# HyperRAM2.net
KiCad netlist of a schematic drawn in Altium Designer
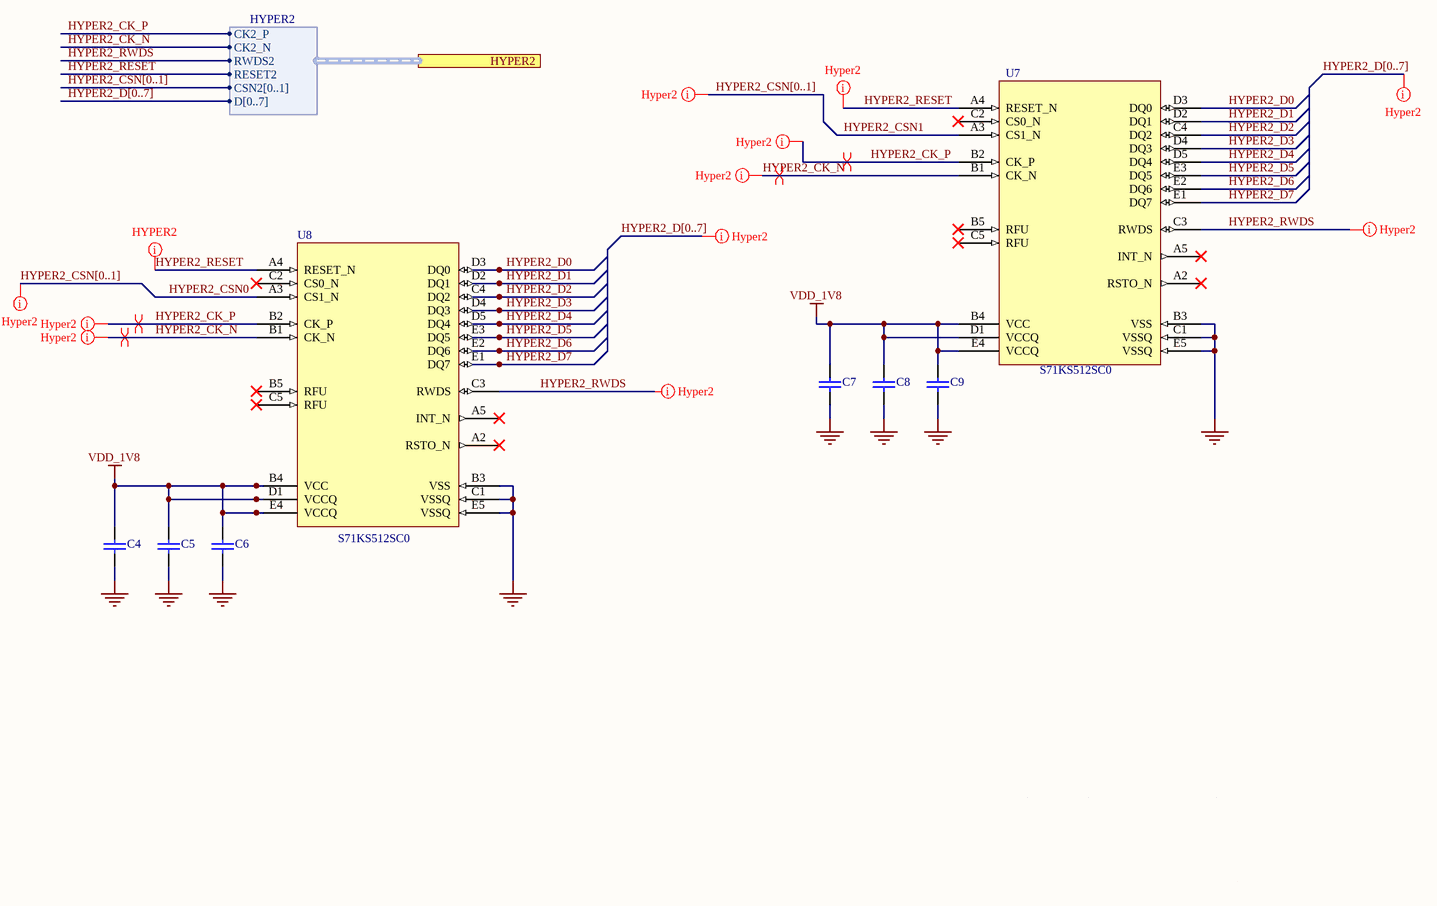
[diagram p0: HyperRAM2.SchDoc]

(export (version "E")
  (design (tool "Eeschema 10.0.6"))
  (components
    (comp (ref "C4")
      (value "VJ0603Y104KNXAO")
      (footprint "CAPC1608X92X38LL15T08")
      (fields (field (name "MANUFACTURER") "Vitramon"))
      (libsource (lib "Altium Content Vault") (part "CAP"))
    )
    (comp (ref "C5")
      (value "VJ0603Y104KNXAO")
      (footprint "CAPC1608X92X38LL15T08")
      (fields (field (name "MANUFACTURER") "Vitramon"))
      (libsource (lib "Altium Content Vault") (part "CAP"))
    )
    (comp (ref "C6")
      (value "VJ0603Y104KNXAO")
      (footprint "CAPC1608X92X38LL15T08")
      (fields (field (name "MANUFACTURER") "Vitramon"))
      (libsource (lib "Altium Content Vault") (part "CAP"))
    )
    (comp (ref "C7")
      (value "VJ0603Y104KNXAO")
      (footprint "CAPC1608X92X38LL15T08")
      (description "100nF")
      (fields (field (name "MANUFACTURER") "Vitramon"))
      (libsource (lib "Altium Content Vault") (part "CAP"))
    )
    (comp (ref "C8")
      (value "VJ0603Y104KNXAO")
      (footprint "CAPC1608X92X38LL15T08")
      (fields (field (name "MANUFACTURER") "Vitramon"))
      (libsource (lib "Altium Content Vault") (part "CAP"))
    )
    (comp (ref "C9")
      (value "VJ0603Y104KNXAO")
      (footprint "CAPC1608X92X38LL15T08")
      (fields (field (name "MANUFACTURER") "Vitramon"))
      (libsource (lib "Altium Content Vault") (part "CAP"))
    )
    (comp (ref "U7")
      (value "S71KS512SC0")
      (footprint "FBGA24_A-130")
      (libsource (lib "Hyperram") (part "S71KS512SC0"))
    )
    (comp (ref "U8")
      (value "S71KS512SC0")
      (footprint "FBGA24_A-130")
      (libsource (lib "Hyperram") (part "S71KS512SC0"))
    )
  )
  (nets
    (net (code "2") (name "/HYPER2_CK_N") (class "Default")
      (node (ref "U7") (pin "B1") (pinfunction "CK_N_B1") (pintype "input"))
      (node (ref "U8") (pin "B1") (pinfunction "CK_N_B1") (pintype "input"))
    )
    (net (code "3") (name "/HYPER2_CK_P") (class "Default")
      (node (ref "U7") (pin "B2") (pinfunction "CK_P_B2") (pintype "input"))
      (node (ref "U8") (pin "B2") (pinfunction "CK_P_B2") (pintype "input"))
    )
    (net (code "4") (name "/HYPER2_CSN0") (class "Default")
      (node (ref "U8") (pin "A3") (pinfunction "CS1_N_A3") (pintype "input"))
    )
    (net (code "5") (name "/HYPER2_CSN1") (class "Default")
      (node (ref "U7") (pin "A3") (pinfunction "CS1_N_A3") (pintype "input"))
    )
    (net (code "7") (name "/HYPER2_D0") (class "Default")
      (node (ref "U7") (pin "D3") (pinfunction "DQ0_D3") (pintype "bidirectional"))
      (node (ref "U8") (pin "D3") (pinfunction "DQ0_D3") (pintype "bidirectional"))
    )
    (net (code "8") (name "/HYPER2_D1") (class "Default")
      (node (ref "U7") (pin "D2") (pinfunction "DQ1_D2") (pintype "bidirectional"))
      (node (ref "U8") (pin "D2") (pinfunction "DQ1_D2") (pintype "bidirectional"))
    )
    (net (code "9") (name "/HYPER2_D2") (class "Default")
      (node (ref "U7") (pin "C4") (pinfunction "DQ2_C4") (pintype "bidirectional"))
      (node (ref "U8") (pin "C4") (pinfunction "DQ2_C4") (pintype "bidirectional"))
    )
    (net (code "10") (name "/HYPER2_D3") (class "Default")
      (node (ref "U7") (pin "D4") (pinfunction "DQ3_D4") (pintype "bidirectional"))
      (node (ref "U8") (pin "D4") (pinfunction "DQ3_D4") (pintype "bidirectional"))
    )
    (net (code "11") (name "/HYPER2_D4") (class "Default")
      (node (ref "U7") (pin "D5") (pinfunction "DQ4_D5") (pintype "bidirectional"))
      (node (ref "U8") (pin "D5") (pinfunction "DQ4_D5") (pintype "bidirectional"))
    )
    (net (code "12") (name "/HYPER2_D5") (class "Default")
      (node (ref "U7") (pin "E3") (pinfunction "DQ5_E3") (pintype "bidirectional"))
      (node (ref "U8") (pin "E3") (pinfunction "DQ5_E3") (pintype "bidirectional"))
    )
    (net (code "13") (name "/HYPER2_D6") (class "Default")
      (node (ref "U7") (pin "E2") (pinfunction "DQ6_E2") (pintype "bidirectional"))
      (node (ref "U8") (pin "E2") (pinfunction "DQ6_E2") (pintype "bidirectional"))
    )
    (net (code "14") (name "/HYPER2_D7") (class "Default")
      (node (ref "U7") (pin "E1") (pinfunction "DQ7_E1") (pintype "bidirectional"))
      (node (ref "U8") (pin "E1") (pinfunction "DQ7_E1") (pintype "bidirectional"))
    )
    (net (code "16") (name "/HYPER2_RESET") (class "Default")
      (node (ref "U7") (pin "A4") (pinfunction "RESET_N_A4") (pintype "input"))
      (node (ref "U8") (pin "A4") (pinfunction "RESET_N_A4") (pintype "input"))
    )
    (net (code "17") (name "/HYPER2_RWDS") (class "Default")
      (node (ref "U7") (pin "C3") (pinfunction "RWDS_C3") (pintype "bidirectional"))
      (node (ref "U8") (pin "C3") (pinfunction "RWDS_C3") (pintype "bidirectional"))
    )
    (net (code "19") (name "GND") (class "Default")
      (node (ref "C4") (pin "1") (pinfunction "1_1") (pintype "passive"))
      (node (ref "C5") (pin "1") (pinfunction "1_1") (pintype "passive"))
      (node (ref "C6") (pin "1") (pinfunction "1_1") (pintype "passive"))
      (node (ref "C7") (pin "1") (pinfunction "1_1") (pintype "passive"))
      (node (ref "C8") (pin "1") (pinfunction "1_1") (pintype "passive"))
      (node (ref "C9") (pin "1") (pinfunction "1_1") (pintype "passive"))
      (node (ref "U7") (pin "B3") (pinfunction "VSS_B3") (pintype "input"))
      (node (ref "U7") (pin "C1") (pinfunction "VSSQ_C1") (pintype "input"))
      (node (ref "U7") (pin "E5") (pinfunction "VSSQ_E5") (pintype "input"))
      (node (ref "U8") (pin "B3") (pinfunction "VSS_B3") (pintype "input"))
      (node (ref "U8") (pin "C1") (pinfunction "VSSQ_C1") (pintype "input"))
      (node (ref "U8") (pin "E5") (pinfunction "VSSQ_E5") (pintype "input"))
    )
    (net (code "20") (name "VDD_1V8") (class "Default")
      (node (ref "C4") (pin "2") (pinfunction "2_2") (pintype "passive"))
      (node (ref "C5") (pin "2") (pinfunction "2_2") (pintype "passive"))
      (node (ref "C6") (pin "2") (pinfunction "2_2") (pintype "passive"))
      (node (ref "C7") (pin "2") (pinfunction "2_2") (pintype "passive"))
      (node (ref "C8") (pin "2") (pinfunction "2_2") (pintype "passive"))
      (node (ref "C9") (pin "2") (pinfunction "2_2") (pintype "passive"))
      (node (ref "U7") (pin "B4") (pinfunction "VCC_B4") (pintype "power_in"))
      (node (ref "U7") (pin "D1") (pinfunction "VCCQ_D1") (pintype "power_in"))
      (node (ref "U7") (pin "E4") (pinfunction "VCCQ_E4") (pintype "power_in"))
      (node (ref "U8") (pin "B4") (pinfunction "VCC_B4") (pintype "power_in"))
      (node (ref "U8") (pin "D1") (pinfunction "VCCQ_D1") (pintype "power_in"))
      (node (ref "U8") (pin "E4") (pinfunction "VCCQ_E4") (pintype "power_in"))
    )
    (net (code "21") (name "unconnected-(U7-CS0_N-PadC2)") (class "Default")
      (node (ref "U7") (pin "C2") (pinfunction "CS0_N_C2") (pintype "input+no_connect"))
    )
    (net (code "22") (name "unconnected-(U7-INT_N-PadA5)") (class "Default")
      (node (ref "U7") (pin "A5") (pinfunction "INT_N_A5") (pintype "output+no_connect"))
    )
    (net (code "23") (name "unconnected-(U7-RFU-PadB5)") (class "Default")
      (node (ref "U7") (pin "B5") (pinfunction "RFU_B5") (pintype "input+no_connect"))
    )
    (net (code "24") (name "unconnected-(U7-RFU-PadC5)") (class "Default")
      (node (ref "U7") (pin "C5") (pinfunction "RFU_C5") (pintype "input+no_connect"))
    )
    (net (code "25") (name "unconnected-(U7-RSTO_N-PadA2)") (class "Default")
      (node (ref "U7") (pin "A2") (pinfunction "RSTO_N_A2") (pintype "output+no_connect"))
    )
    (net (code "26") (name "unconnected-(U8-CS0_N-PadC2)") (class "Default")
      (node (ref "U8") (pin "C2") (pinfunction "CS0_N_C2") (pintype "input+no_connect"))
    )
    (net (code "27") (name "unconnected-(U8-INT_N-PadA5)") (class "Default")
      (node (ref "U8") (pin "A5") (pinfunction "INT_N_A5") (pintype "output+no_connect"))
    )
    (net (code "28") (name "unconnected-(U8-RFU-PadB5)") (class "Default")
      (node (ref "U8") (pin "B5") (pinfunction "RFU_B5") (pintype "input+no_connect"))
    )
    (net (code "29") (name "unconnected-(U8-RFU-PadC5)") (class "Default")
      (node (ref "U8") (pin "C5") (pinfunction "RFU_C5") (pintype "input+no_connect"))
    )
    (net (code "30") (name "unconnected-(U8-RSTO_N-PadA2)") (class "Default")
      (node (ref "U8") (pin "A2") (pinfunction "RSTO_N_A2") (pintype "output+no_connect"))
    )
  )
)
